# PROCESSING_UNIT.net
KiCad netlist of a schematic drawn in EAGLE
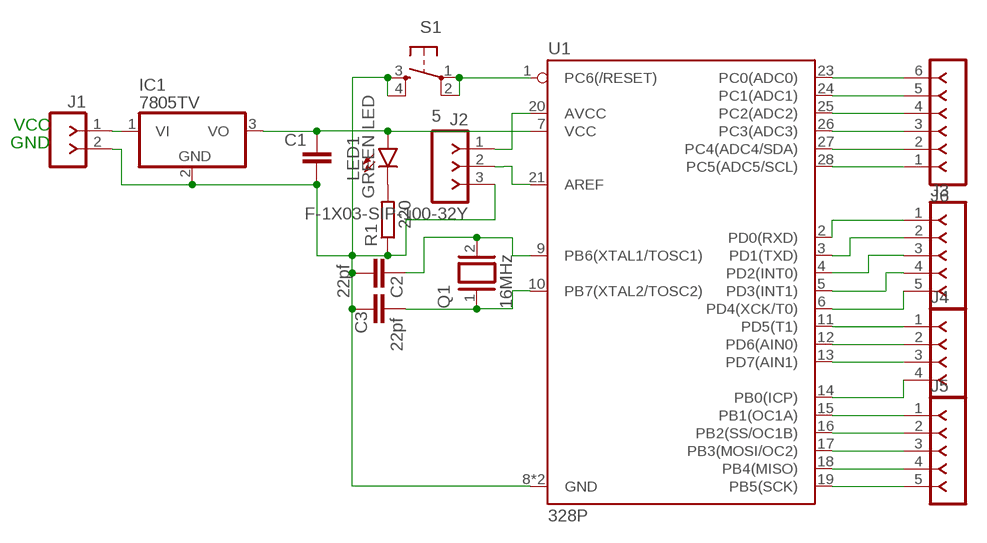
[diagram p0: schematic, sheet 1]

(export (version "E")
  (design (tool "Eeschema 10.0.6"))
  (components
    (comp (ref "C1")
      (value "1uf")
      (footprint "eagle-import:C025-025X050")
      (libsource (lib "eagle-import") (part "C-EU025-025X050"))
    )
    (comp (ref "C2")
      (value "22pf")
      (footprint "eagle-import:C025-025X050")
      (libsource (lib "eagle-import") (part "C-EU025-025X050"))
    )
    (comp (ref "C3")
      (value "22pf")
      (footprint "eagle-import:C025-025X050")
      (libsource (lib "eagle-import") (part "C-EU025-025X050"))
    )
    (comp (ref "IC1")
      (value "7805TV")
      (footprint "eagle-import:TO220V")
      (libsource (lib "eagle-import") (part "78TV05"))
    )
    (comp (ref "J1")
      (value "F-1X02-SIP-100-32Y")
      (footprint "eagle-import:SIP-100-02-32Y")
      (libsource (lib "eagle-import") (part "F-1X02-SIP-100-32Y"))
    )
    (comp (ref "J2")
      (value "F-1X03-SIP-100-32Y")
      (footprint "eagle-import:SIP-100-03-32Y")
      (libsource (lib "eagle-import") (part "F-1X03-SIP-100-32Y"))
    )
    (comp (ref "J3")
      (value "F-1X05-SIP-100-32Y")
      (footprint "eagle-import:SIP-100-05-32Y")
      (libsource (lib "eagle-import") (part "F-1X05-SIP-100-32Y"))
    )
    (comp (ref "J4")
      (value "F-1X04-SIP-100-32Y")
      (footprint "eagle-import:SIP-100-04-32Y")
      (libsource (lib "eagle-import") (part "F-1X04-SIP-100-32Y"))
    )
    (comp (ref "J5")
      (value "F-1X05-SIP-100-32Y")
      (footprint "eagle-import:SIP-100-05-32Y")
      (libsource (lib "eagle-import") (part "F-1X05-SIP-100-32Y"))
    )
    (comp (ref "J6")
      (value "F-1X06-SIP-100-32Y")
      (footprint "eagle-import:SIP-100-06-32Y")
      (libsource (lib "eagle-import") (part "F-1X06-SIP-100-32Y"))
    )
    (comp (ref "LED1")
      (value "GREEN LED")
      (footprint "eagle-import:SML0603")
      (libsource (lib "eagle-import") (part "LEDSML0603"))
    )
    (comp (ref "Q1")
      (value "16MHz")
      (footprint "eagle-import:QS")
      (libsource (lib "eagle-import") (part "XTAL/S"))
    )
    (comp (ref "R1")
      (value "220")
      (footprint "eagle-import:0204_7")
      (libsource (lib "eagle-import") (part "R-EU_0204/7"))
    )
    (comp (ref "S1")
      (value "5")
      (footprint "eagle-import:TACTILE-PTH")
      (libsource (lib "eagle-import") (part "TAC_SWITCHPTH"))
    )
    (comp (ref "U1")
      (value "328P")
      (footprint "eagle-import:DIP28")
      (libsource (lib "eagle-import") (part "ATMEGA328P_PDIP"))
    )
  )
  (nets
    (net (code "1") (name "Net-(IC1-GND)") (class "Default")
      (node (ref "C1") (pin "2") (pinfunction "2_2") (pintype "passive"))
      (node (ref "C2") (pin "1") (pinfunction "1_1") (pintype "passive"))
      (node (ref "C3") (pin "1") (pinfunction "1_1") (pintype "passive"))
      (node (ref "IC1") (pin "2") (pinfunction "GND_2") (pintype "passive"))
      (node (ref "J1") (pin "2") (pinfunction "2_2") (pintype "passive"))
      (node (ref "J2") (pin "3") (pinfunction "3_3") (pintype "passive"))
      (node (ref "R1") (pin "1") (pinfunction "1_1") (pintype "passive"))
      (node (ref "S1") (pin "3") (pinfunction "3_3") (pintype "passive"))
      (node (ref "S1") (pin "4") (pinfunction "4_4") (pintype "passive"))
      (node (ref "U1") (pin "22") (pinfunction "GND_22") (pintype "bidirectional"))
      (node (ref "U1") (pin "8") (pinfunction "GND_8") (pintype "bidirectional"))
    )
    (net (code "2") (name "Net-(IC1-VI)") (class "Default")
      (node (ref "IC1") (pin "1") (pinfunction "VI_1") (pintype "input"))
      (node (ref "J1") (pin "1") (pinfunction "1_1") (pintype "passive"))
    )
    (net (code "3") (name "Net-(IC1-VO)") (class "Default")
      (node (ref "C1") (pin "1") (pinfunction "1_1") (pintype "passive"))
      (node (ref "IC1") (pin "3") (pinfunction "VO_3") (pintype "passive"))
      (node (ref "LED1") (pin "A") (pinfunction "A_A") (pintype "passive"))
      (node (ref "U1") (pin "7") (pinfunction "VCC_7") (pintype "bidirectional"))
    )
    (net (code "4") (name "Net-(LED1-PadC)") (class "Default")
      (node (ref "LED1") (pin "C") (pinfunction "C_C") (pintype "passive"))
      (node (ref "R1") (pin "2") (pinfunction "2_2") (pintype "passive"))
    )
    (net (code "5") (name "Net-(U1-AREF)") (class "Default")
      (node (ref "J2") (pin "2") (pinfunction "2_2") (pintype "passive"))
      (node (ref "U1") (pin "21") (pinfunction "AREF_21") (pintype "bidirectional"))
    )
    (net (code "6") (name "Net-(U1-AVCC)") (class "Default")
      (node (ref "J2") (pin "1") (pinfunction "1_1") (pintype "passive"))
      (node (ref "U1") (pin "20") (pinfunction "AVCC_20") (pintype "bidirectional"))
    )
    (net (code "7") (name "Net-(U1-PB0(ICP))") (class "Default")
      (node (ref "J4") (pin "4") (pinfunction "4_4") (pintype "passive"))
      (node (ref "U1") (pin "14") (pinfunction "PB0(ICP)_14") (pintype "bidirectional"))
    )
    (net (code "8") (name "Net-(U1-PB1(OC1A))") (class "Default")
      (node (ref "J5") (pin "1") (pinfunction "1_1") (pintype "passive"))
      (node (ref "U1") (pin "15") (pinfunction "PB1(OC1A)_15") (pintype "bidirectional"))
    )
    (net (code "9") (name "Net-(U1-PB2(SS{slash}OC1B))") (class "Default")
      (node (ref "J5") (pin "2") (pinfunction "2_2") (pintype "passive"))
      (node (ref "U1") (pin "16") (pinfunction "PB2(SS/OC1B)_16") (pintype "bidirectional"))
    )
    (net (code "10") (name "Net-(U1-PB3(MOSI{slash}OC2))") (class "Default")
      (node (ref "J5") (pin "3") (pinfunction "3_3") (pintype "passive"))
      (node (ref "U1") (pin "17") (pinfunction "PB3(MOSI/OC2)_17") (pintype "bidirectional"))
    )
    (net (code "11") (name "Net-(U1-PB4(MISO))") (class "Default")
      (node (ref "J5") (pin "4") (pinfunction "4_4") (pintype "passive"))
      (node (ref "U1") (pin "18") (pinfunction "PB4(MISO)_18") (pintype "bidirectional"))
    )
    (net (code "12") (name "Net-(U1-PB5(SCK))") (class "Default")
      (node (ref "J5") (pin "5") (pinfunction "5_5") (pintype "passive"))
      (node (ref "U1") (pin "19") (pinfunction "PB5(SCK)_19") (pintype "bidirectional"))
    )
    (net (code "13") (name "Net-(U1-PB6(XTAL1{slash}TOSC1))") (class "Default")
      (node (ref "C2") (pin "2") (pinfunction "2_2") (pintype "passive"))
      (node (ref "Q1") (pin "2") (pinfunction "2_2") (pintype "passive"))
      (node (ref "U1") (pin "9") (pinfunction "PB6(XTAL1/TOSC1)_9") (pintype "bidirectional"))
    )
    (net (code "14") (name "Net-(U1-PB7(XTAL2{slash}TOSC2))") (class "Default")
      (node (ref "C3") (pin "2") (pinfunction "2_2") (pintype "passive"))
      (node (ref "Q1") (pin "1") (pinfunction "1_1") (pintype "passive"))
      (node (ref "U1") (pin "10") (pinfunction "PB7(XTAL2/TOSC2)_10") (pintype "bidirectional"))
    )
    (net (code "15") (name "Net-(U1-PC0(ADC0))") (class "Default")
      (node (ref "J6") (pin "6") (pinfunction "6_6") (pintype "passive"))
      (node (ref "U1") (pin "23") (pinfunction "PC0(ADC0)_23") (pintype "bidirectional"))
    )
    (net (code "16") (name "Net-(U1-PC1(ADC1))") (class "Default")
      (node (ref "J6") (pin "5") (pinfunction "5_5") (pintype "passive"))
      (node (ref "U1") (pin "24") (pinfunction "PC1(ADC1)_24") (pintype "bidirectional"))
    )
    (net (code "17") (name "Net-(U1-PC2(ADC2))") (class "Default")
      (node (ref "J6") (pin "4") (pinfunction "4_4") (pintype "passive"))
      (node (ref "U1") (pin "25") (pinfunction "PC2(ADC2)_25") (pintype "bidirectional"))
    )
    (net (code "18") (name "Net-(U1-PC3(ADC3))") (class "Default")
      (node (ref "J6") (pin "3") (pinfunction "3_3") (pintype "passive"))
      (node (ref "U1") (pin "26") (pinfunction "PC3(ADC3)_26") (pintype "bidirectional"))
    )
    (net (code "19") (name "Net-(U1-PC4(ADC4{slash}SDA))") (class "Default")
      (node (ref "J6") (pin "2") (pinfunction "2_2") (pintype "passive"))
      (node (ref "U1") (pin "27") (pinfunction "PC4(ADC4/SDA)_27") (pintype "bidirectional"))
    )
    (net (code "20") (name "Net-(U1-PC5(ADC5{slash}SCL))") (class "Default")
      (node (ref "J6") (pin "1") (pinfunction "1_1") (pintype "passive"))
      (node (ref "U1") (pin "28") (pinfunction "PC5(ADC5/SCL)_28") (pintype "bidirectional"))
    )
    (net (code "21") (name "Net-(U1-PC6({slash}RESET))") (class "Default")
      (node (ref "S1") (pin "1") (pinfunction "1_1") (pintype "passive"))
      (node (ref "S1") (pin "2") (pinfunction "2_2") (pintype "passive"))
      (node (ref "U1") (pin "1") (pinfunction "PC6(/RESET)_1") (pintype "bidirectional"))
    )
    (net (code "22") (name "Net-(U1-PD0(RXD))") (class "Default")
      (node (ref "J3") (pin "1") (pinfunction "1_1") (pintype "passive"))
      (node (ref "U1") (pin "2") (pinfunction "PD0(RXD)_2") (pintype "bidirectional"))
    )
    (net (code "23") (name "Net-(U1-PD1(TXD))") (class "Default")
      (node (ref "J3") (pin "2") (pinfunction "2_2") (pintype "passive"))
      (node (ref "U1") (pin "3") (pinfunction "PD1(TXD)_3") (pintype "bidirectional"))
    )
    (net (code "24") (name "Net-(U1-PD2(INT0))") (class "Default")
      (node (ref "J3") (pin "3") (pinfunction "3_3") (pintype "passive"))
      (node (ref "U1") (pin "4") (pinfunction "PD2(INT0)_4") (pintype "bidirectional"))
    )
    (net (code "25") (name "Net-(U1-PD3(INT1))") (class "Default")
      (node (ref "J3") (pin "4") (pinfunction "4_4") (pintype "passive"))
      (node (ref "U1") (pin "5") (pinfunction "PD3(INT1)_5") (pintype "bidirectional"))
    )
    (net (code "26") (name "Net-(U1-PD4(XCK{slash}T0))") (class "Default")
      (node (ref "J3") (pin "5") (pinfunction "5_5") (pintype "passive"))
      (node (ref "U1") (pin "6") (pinfunction "PD4(XCK/T0)_6") (pintype "bidirectional"))
    )
    (net (code "27") (name "Net-(U1-PD5(T1))") (class "Default")
      (node (ref "J4") (pin "1") (pinfunction "1_1") (pintype "passive"))
      (node (ref "U1") (pin "11") (pinfunction "PD5(T1)_11") (pintype "bidirectional"))
    )
    (net (code "28") (name "Net-(U1-PD6(AIN0))") (class "Default")
      (node (ref "J4") (pin "2") (pinfunction "2_2") (pintype "passive"))
      (node (ref "U1") (pin "12") (pinfunction "PD6(AIN0)_12") (pintype "bidirectional"))
    )
    (net (code "29") (name "Net-(U1-PD7(AIN1))") (class "Default")
      (node (ref "J4") (pin "3") (pinfunction "3_3") (pintype "passive"))
      (node (ref "U1") (pin "13") (pinfunction "PD7(AIN1)_13") (pintype "bidirectional"))
    )
  )
)
